# PCA9685_sheet.net
KiCad netlist of a schematic drawn in Altium Designer
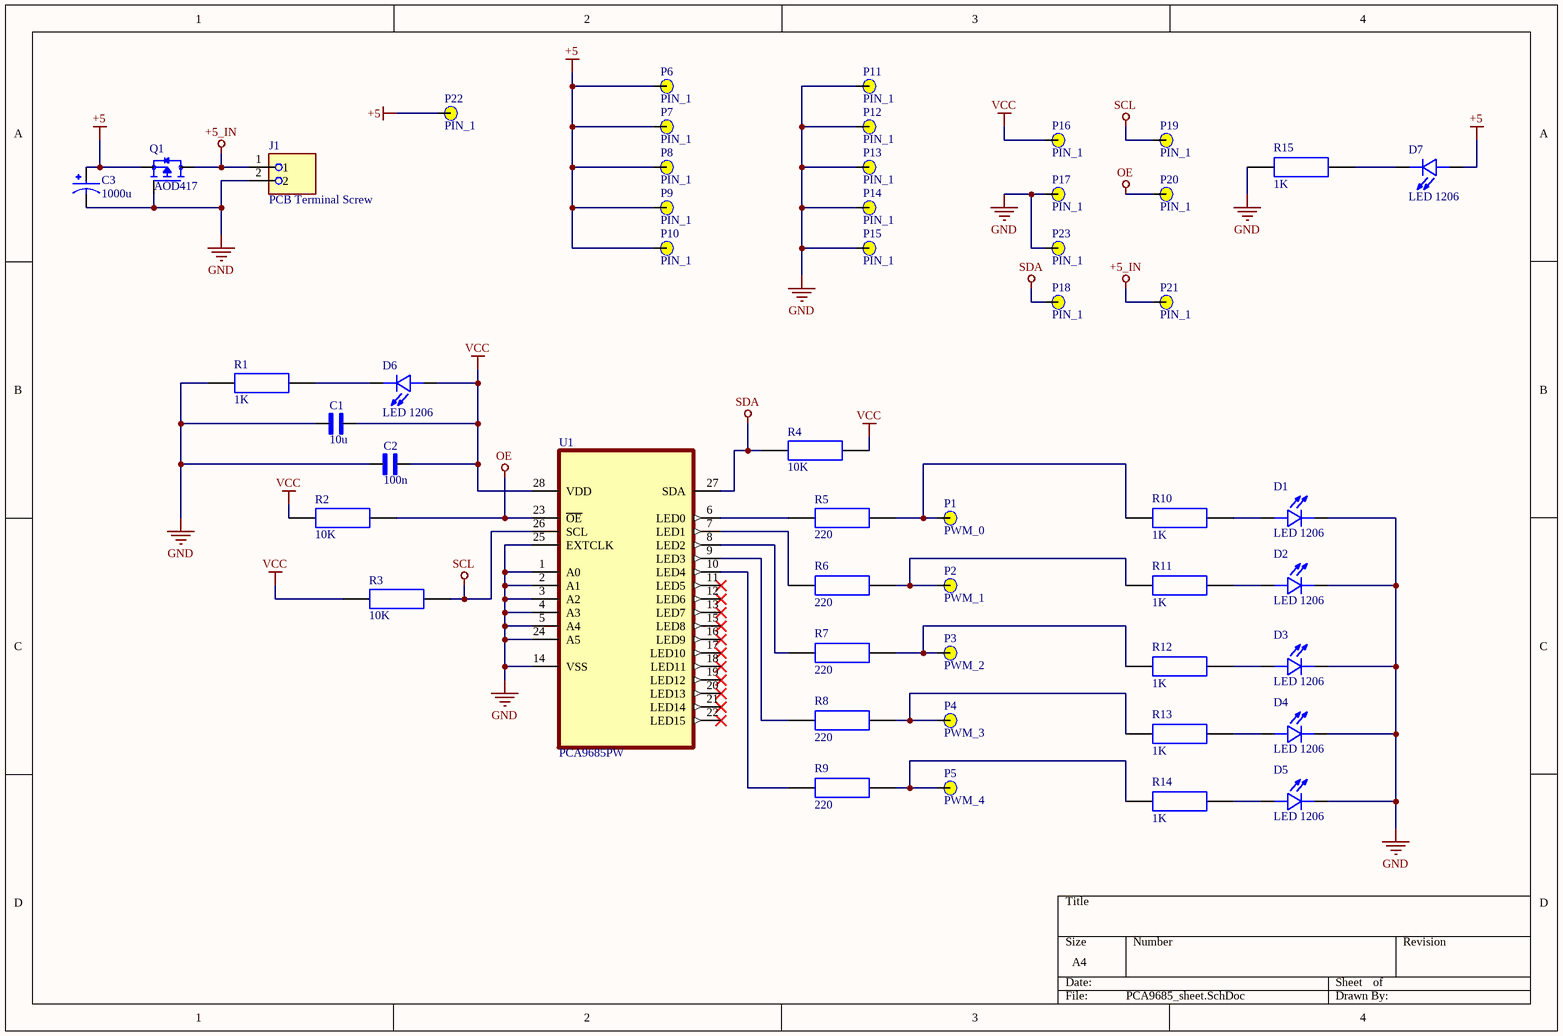
[diagram p0: PCA9685_sheet.SchDoc]

(export (version "E")
  (design (tool "Eeschema 10.0.6"))
  (components
    (comp (ref "C1")
      (value "10u")
      (footprint "Capacitor 1206")
      (fields (field (name "MF") "AVX") (field (name "MP") "12061C225K4T2A"))
      (libsource (lib "PCA_9685_lib") (part "Capacitor 1206"))
    )
    (comp (ref "C2")
      (value "100n")
      (footprint "Capacitor 1206")
      (fields (field (name "MF") "AVX") (field (name "MP") "12061C225K4T2A"))
      (libsource (lib "PCA_9685_lib") (part "Capacitor 1206"))
    )
    (comp (ref "C3")
      (value "1000u")
      (footprint "Electrolytic capacitor")
      (fields (field (name "MP") "EEUFR1A102LB") (field (name "MF") "Panasonic"))
      (libsource (lib "PCA_9685_lib") (part "Electrolytic capacitor"))
    )
    (comp (ref "D1")
      (value "LED 1206")
      (footprint "LED 1206")
      (fields (field (name "MF") "Lite-On Inc.") (field (name "MP") "LTST-C230KGKT"))
      (libsource (lib "PCA_9685_lib") (part "LED 1206"))
    )
    (comp (ref "D2")
      (value "LED 1206")
      (footprint "LED 1206")
      (fields (field (name "MF") "Lite-On Inc.") (field (name "MP") "LTST-C230KGKT"))
      (libsource (lib "PCA_9685_lib") (part "LED 1206"))
    )
    (comp (ref "D3")
      (value "LED 1206")
      (footprint "LED 1206")
      (fields (field (name "MF") "Lite-On Inc.") (field (name "MP") "LTST-C230KGKT"))
      (libsource (lib "PCA_9685_lib") (part "LED 1206"))
    )
    (comp (ref "D4")
      (value "LED 1206")
      (footprint "LED 1206")
      (fields (field (name "MF") "Lite-On Inc.") (field (name "MP") "LTST-C230KGKT"))
      (libsource (lib "PCA_9685_lib") (part "LED 1206"))
    )
    (comp (ref "D5")
      (value "LED 1206")
      (footprint "LED 1206")
      (fields (field (name "MF") "Lite-On Inc.") (field (name "MP") "LTST-C230KGKT"))
      (libsource (lib "PCA_9685_lib") (part "LED 1206"))
    )
    (comp (ref "D6")
      (value "LED 1206")
      (footprint "LED 1206")
      (fields (field (name "MF") "Lite-On Inc.") (field (name "MP") "LTST-C230KGKT"))
      (libsource (lib "") (part "LED 1206_1"))
    )
    (comp (ref "D7")
      (value "LED 1206")
      (footprint "LED 1206")
      (fields (field (name "MF") "Lite-On Inc.") (field (name "MP") "LTST-C230KGKT"))
      (libsource (lib "") (part "LED 1206_1"))
    )
    (comp (ref "J1")
      (value "PCB Terminal Screw")
      (footprint "PCB Terminal Screw")
      (fields (field (name "MF") "Phoenix Contact") (field (name "MP") "1729128"))
      (libsource (lib "PCA_9685_lib") (part "PCB Terminal Screw"))
    )
    (comp (ref "P1") (value "PWM_0") (footprint "PCB_Pin_1") (libsource (lib "PCA_9685_lib") (part "PIN_1")))
    (comp (ref "P2") (value "PWM_1") (footprint "PCB_Pin_1") (libsource (lib "PCA_9685_lib") (part "PIN_1")))
    (comp (ref "P3") (value "PWM_2") (footprint "PCB_Pin_1") (libsource (lib "PCA_9685_lib") (part "PIN_1")))
    (comp (ref "P4") (value "PWM_3") (footprint "PCB_Pin_1") (libsource (lib "PCA_9685_lib") (part "PIN_1")))
    (comp (ref "P5") (value "PWM_4") (footprint "PCB_Pin_1") (libsource (lib "PCA_9685_lib") (part "PIN_1")))
    (comp (ref "P6") (value "PIN_1") (footprint "PCB_Pin_1") (libsource (lib "PCA_9685_lib") (part "PIN_1")))
    (comp (ref "P7") (value "PIN_1") (footprint "PCB_Pin_1") (libsource (lib "PCA_9685_lib") (part "PIN_1")))
    (comp (ref "P8") (value "PIN_1") (footprint "PCB_Pin_1") (libsource (lib "PCA_9685_lib") (part "PIN_1")))
    (comp (ref "P9") (value "PIN_1") (footprint "PCB_Pin_1") (libsource (lib "PCA_9685_lib") (part "PIN_1")))
    (comp (ref "P10") (value "PIN_1") (footprint "PCB_Pin_1") (libsource (lib "PCA_9685_lib") (part "PIN_1")))
    (comp (ref "P11") (value "PIN_1") (footprint "PCB_Pin_1") (libsource (lib "PCA_9685_lib") (part "PIN_1")))
    (comp (ref "P12") (value "PIN_1") (footprint "PCB_Pin_1") (libsource (lib "PCA_9685_lib") (part "PIN_1")))
    (comp (ref "P13") (value "PIN_1") (footprint "PCB_Pin_1") (libsource (lib "PCA_9685_lib") (part "PIN_1")))
    (comp (ref "P14") (value "PIN_1") (footprint "PCB_Pin_1") (libsource (lib "PCA_9685_lib") (part "PIN_1")))
    (comp (ref "P15") (value "PIN_1") (footprint "PCB_Pin_1") (libsource (lib "PCA_9685_lib") (part "PIN_1")))
    (comp (ref "P16") (value "PIN_1") (footprint "PCB_Pin_1") (libsource (lib "PCA_9685_lib") (part "PIN_1")))
    (comp (ref "P17") (value "PIN_1") (footprint "PCB_Pin_1") (libsource (lib "PCA_9685_lib") (part "PIN_1")))
    (comp (ref "P18") (value "PIN_1") (footprint "PCB_Pin_1") (libsource (lib "PCA_9685_lib") (part "PIN_1")))
    (comp (ref "P19") (value "PIN_1") (footprint "PCB_Pin_1") (libsource (lib "PCA_9685_lib") (part "PIN_1")))
    (comp (ref "P20") (value "PIN_1") (footprint "PCB_Pin_1") (libsource (lib "PCA_9685_lib") (part "PIN_1")))
    (comp (ref "P21") (value "PIN_1") (footprint "PCB_Pin_1") (libsource (lib "PCA_9685_lib") (part "PIN_1")))
    (comp (ref "P22") (value "PIN_1") (footprint "PCB_Pin_1") (libsource (lib "PCA_9685_lib") (part "PIN_1")))
    (comp (ref "P23") (value "PIN_1") (footprint "PCB_Pin_1") (libsource (lib "PCA_9685_lib") (part "PIN_1")))
    (comp (ref "Q1")
      (value "AOD417")
      (footprint "PCA_9685_lib:Transistor AOD417")
      (fields (field (name "MF") "Alpha &"))
      (libsource (lib "PCA_9685_lib") (part "Transistor AOD417"))
    )
    (comp (ref "R1")
      (value "1K")
      (footprint "PCA_9685_lib:Resistor 1206")
      (fields (field (name "MP") "ERJU08F4703V"))
      (libsource (lib "PCA_9685_lib") (part "Resistor 1206"))
    )
    (comp (ref "R2")
      (value "10K")
      (footprint "PCA_9685_lib:Resistor 1206")
      (fields (field (name "MP") "ERJU08F4703V"))
      (libsource (lib "PCA_9685_lib") (part "Resistor 1206"))
    )
    (comp (ref "R3")
      (value "10K")
      (footprint "PCA_9685_lib:Resistor 1206")
      (fields (field (name "MP") "ERJU08F4703V"))
      (libsource (lib "PCA_9685_lib") (part "Resistor 1206"))
    )
    (comp (ref "R4")
      (value "10K")
      (footprint "PCA_9685_lib:Resistor 1206")
      (fields (field (name "MP") "ERJU08F4703V"))
      (libsource (lib "PCA_9685_lib") (part "Resistor 1206"))
    )
    (comp (ref "R5")
      (value "220")
      (footprint "PCA_9685_lib:Resistor 1206")
      (fields (field (name "MP") "ERJU08F4703V"))
      (libsource (lib "PCA_9685_lib") (part "Resistor 1206"))
    )
    (comp (ref "R6")
      (value "220")
      (footprint "PCA_9685_lib:Resistor 1206")
      (fields (field (name "MP") "ERJU08F4703V"))
      (libsource (lib "PCA_9685_lib") (part "Resistor 1206"))
    )
    (comp (ref "R7")
      (value "220")
      (footprint "PCA_9685_lib:Resistor 1206")
      (fields (field (name "MP") "ERJU08F4703V"))
      (libsource (lib "PCA_9685_lib") (part "Resistor 1206"))
    )
    (comp (ref "R8")
      (value "220")
      (footprint "PCA_9685_lib:Resistor 1206")
      (fields (field (name "MP") "ERJU08F4703V"))
      (libsource (lib "PCA_9685_lib") (part "Resistor 1206"))
    )
    (comp (ref "R9")
      (value "220")
      (footprint "PCA_9685_lib:Resistor 1206")
      (fields (field (name "MP") "ERJU08F4703V"))
      (libsource (lib "PCA_9685_lib") (part "Resistor 1206"))
    )
    (comp (ref "R10")
      (value "1K")
      (footprint "PCA_9685_lib:Resistor 1206")
      (fields (field (name "MP") "ERJU08F4703V"))
      (libsource (lib "PCA_9685_lib") (part "Resistor 1206"))
    )
    (comp (ref "R11")
      (value "1K")
      (footprint "PCA_9685_lib:Resistor 1206")
      (fields (field (name "MP") "ERJU08F4703V"))
      (libsource (lib "PCA_9685_lib") (part "Resistor 1206"))
    )
    (comp (ref "R12")
      (value "1K")
      (footprint "PCA_9685_lib:Resistor 1206")
      (fields (field (name "MP") "ERJU08F4703V"))
      (libsource (lib "PCA_9685_lib") (part "Resistor 1206"))
    )
    (comp (ref "R13")
      (value "1K")
      (footprint "PCA_9685_lib:Resistor 1206")
      (fields (field (name "MP") "ERJU08F4703V"))
      (libsource (lib "PCA_9685_lib") (part "Resistor 1206"))
    )
    (comp (ref "R14")
      (value "1K")
      (footprint "PCA_9685_lib:Resistor 1206")
      (fields (field (name "MP") "ERJU08F4703V"))
      (libsource (lib "PCA_9685_lib") (part "Resistor 1206"))
    )
    (comp (ref "R15")
      (value "1K")
      (footprint "PCA_9685_lib:Resistor 1206")
      (fields (field (name "MP") "ERJU08F4703V"))
      (libsource (lib "PCA_9685_lib") (part "Resistor 1206"))
    )
    (comp (ref "U1")
      (value "PCA9685PW")
      (footprint "PCA9685PW")
      (fields (field (name "MF") "NXP USA") (field (name "MP") "PCA9685PW,118"))
      (libsource (lib "PCA_9685_lib") (part "PCA9685PW"))
    )
  )
  (nets
    (net (code "1") (name "+5") (class "Default")
      (node (ref "C3") (pin "P") (pinfunction "P_P") (pintype "passive"))
      (node (ref "D7") (pin "A") (pinfunction "A_A") (pintype "passive"))
      (node (ref "P10") (pin "0") (pinfunction "Pin_0") (pintype "passive"))
      (node (ref "P22") (pin "0") (pinfunction "Pin_0") (pintype "passive"))
      (node (ref "P6") (pin "0") (pinfunction "Pin_0") (pintype "passive"))
      (node (ref "P7") (pin "0") (pinfunction "Pin_0") (pintype "passive"))
      (node (ref "P8") (pin "0") (pinfunction "Pin_0") (pintype "passive"))
      (node (ref "P9") (pin "0") (pinfunction "Pin_0") (pintype "passive"))
      (node (ref "Q1") (pin "3") (pinfunction "S_3") (pintype "passive"))
    )
    (net (code "2") (name "+5_IN") (class "Default")
      (node (ref "J1") (pin "1") (pinfunction "1_1") (pintype "passive"))
      (node (ref "P21") (pin "0") (pinfunction "Pin_0") (pintype "passive"))
      (node (ref "Q1") (pin "4") (pinfunction "D_4") (pintype "passive"))
    )
    (net (code "3") (name "GND") (class "Default")
      (node (ref "C1") (pin "1") (pinfunction "1_1") (pintype "passive"))
      (node (ref "C2") (pin "1") (pinfunction "1_1") (pintype "passive"))
      (node (ref "C3") (pin "N") (pinfunction "N_N") (pintype "passive"))
      (node (ref "D1") (pin "C") (pinfunction "C_C") (pintype "passive"))
      (node (ref "D2") (pin "C") (pinfunction "C_C") (pintype "passive"))
      (node (ref "D3") (pin "C") (pinfunction "C_C") (pintype "passive"))
      (node (ref "D4") (pin "C") (pinfunction "C_C") (pintype "passive"))
      (node (ref "D5") (pin "C") (pinfunction "C_C") (pintype "passive"))
      (node (ref "J1") (pin "2") (pinfunction "2_2") (pintype "passive"))
      (node (ref "P11") (pin "0") (pinfunction "Pin_0") (pintype "passive"))
      (node (ref "P12") (pin "0") (pinfunction "Pin_0") (pintype "passive"))
      (node (ref "P13") (pin "0") (pinfunction "Pin_0") (pintype "passive"))
      (node (ref "P14") (pin "0") (pinfunction "Pin_0") (pintype "passive"))
      (node (ref "P15") (pin "0") (pinfunction "Pin_0") (pintype "passive"))
      (node (ref "P17") (pin "0") (pinfunction "Pin_0") (pintype "passive"))
      (node (ref "P23") (pin "0") (pinfunction "Pin_0") (pintype "passive"))
      (node (ref "Q1") (pin "1") (pinfunction "G_1") (pintype "passive"))
      (node (ref "R1") (pin "1") (pinfunction "1_1") (pintype "passive"))
      (node (ref "R15") (pin "1") (pinfunction "1_1") (pintype "passive"))
      (node (ref "U1") (pin "1") (pinfunction "A0_1") (pintype "passive"))
      (node (ref "U1") (pin "14") (pinfunction "VSS_14") (pintype "passive"))
      (node (ref "U1") (pin "2") (pinfunction "A1_2") (pintype "passive"))
      (node (ref "U1") (pin "24") (pinfunction "A5_24") (pintype "passive"))
      (node (ref "U1") (pin "25") (pinfunction "EXTCLK_25") (pintype "passive"))
      (node (ref "U1") (pin "3") (pinfunction "A2_3") (pintype "passive"))
      (node (ref "U1") (pin "4") (pinfunction "A3_4") (pintype "passive"))
      (node (ref "U1") (pin "5") (pinfunction "A4_5") (pintype "passive"))
    )
    (net (code "4") (name "Net-(D1-PadA)") (class "Default")
      (node (ref "D1") (pin "A") (pinfunction "A_A") (pintype "passive"))
      (node (ref "R10") (pin "2") (pinfunction "2_2") (pintype "passive"))
    )
    (net (code "5") (name "Net-(D2-PadA)") (class "Default")
      (node (ref "D2") (pin "A") (pinfunction "A_A") (pintype "passive"))
      (node (ref "R11") (pin "2") (pinfunction "2_2") (pintype "passive"))
    )
    (net (code "6") (name "Net-(D3-PadA)") (class "Default")
      (node (ref "D3") (pin "A") (pinfunction "A_A") (pintype "passive"))
      (node (ref "R12") (pin "2") (pinfunction "2_2") (pintype "passive"))
    )
    (net (code "7") (name "Net-(D4-PadA)") (class "Default")
      (node (ref "D4") (pin "A") (pinfunction "A_A") (pintype "passive"))
      (node (ref "R13") (pin "2") (pinfunction "2_2") (pintype "passive"))
    )
    (net (code "8") (name "Net-(D5-PadA)") (class "Default")
      (node (ref "D5") (pin "A") (pinfunction "A_A") (pintype "passive"))
      (node (ref "R14") (pin "2") (pinfunction "2_2") (pintype "passive"))
    )
    (net (code "9") (name "Net-(D6-PadC)") (class "Default")
      (node (ref "D6") (pin "C") (pinfunction "C_C") (pintype "passive"))
      (node (ref "R1") (pin "2") (pinfunction "2_2") (pintype "passive"))
    )
    (net (code "10") (name "Net-(D7-PadC)") (class "Default")
      (node (ref "D7") (pin "C") (pinfunction "C_C") (pintype "passive"))
      (node (ref "R15") (pin "2") (pinfunction "2_2") (pintype "passive"))
    )
    (net (code "11") (name "Net-(P1-Pin)") (class "Default")
      (node (ref "P1") (pin "0") (pinfunction "Pin_0") (pintype "passive"))
      (node (ref "R10") (pin "1") (pinfunction "1_1") (pintype "passive"))
      (node (ref "R5") (pin "2") (pinfunction "2_2") (pintype "passive"))
    )
    (net (code "12") (name "Net-(P2-Pin)") (class "Default")
      (node (ref "P2") (pin "0") (pinfunction "Pin_0") (pintype "passive"))
      (node (ref "R11") (pin "1") (pinfunction "1_1") (pintype "passive"))
      (node (ref "R6") (pin "2") (pinfunction "2_2") (pintype "passive"))
    )
    (net (code "13") (name "Net-(P3-Pin)") (class "Default")
      (node (ref "P3") (pin "0") (pinfunction "Pin_0") (pintype "passive"))
      (node (ref "R12") (pin "1") (pinfunction "1_1") (pintype "passive"))
      (node (ref "R7") (pin "2") (pinfunction "2_2") (pintype "passive"))
    )
    (net (code "14") (name "Net-(P4-Pin)") (class "Default")
      (node (ref "P4") (pin "0") (pinfunction "Pin_0") (pintype "passive"))
      (node (ref "R13") (pin "1") (pinfunction "1_1") (pintype "passive"))
      (node (ref "R8") (pin "2") (pinfunction "2_2") (pintype "passive"))
    )
    (net (code "15") (name "Net-(P5-Pin)") (class "Default")
      (node (ref "P5") (pin "0") (pinfunction "Pin_0") (pintype "passive"))
      (node (ref "R14") (pin "1") (pinfunction "1_1") (pintype "passive"))
      (node (ref "R9") (pin "2") (pinfunction "2_2") (pintype "passive"))
    )
    (net (code "16") (name "Net-(U1-LED0)") (class "Default")
      (node (ref "R5") (pin "1") (pinfunction "1_1") (pintype "passive"))
      (node (ref "U1") (pin "6") (pinfunction "LED0_6") (pintype "output"))
    )
    (net (code "17") (name "Net-(U1-LED1)") (class "Default")
      (node (ref "R6") (pin "1") (pinfunction "1_1") (pintype "passive"))
      (node (ref "U1") (pin "7") (pinfunction "LED1_7") (pintype "output"))
    )
    (net (code "18") (name "Net-(U1-LED2)") (class "Default")
      (node (ref "R7") (pin "1") (pinfunction "1_1") (pintype "passive"))
      (node (ref "U1") (pin "8") (pinfunction "LED2_8") (pintype "output"))
    )
    (net (code "19") (name "Net-(U1-LED3)") (class "Default")
      (node (ref "R8") (pin "1") (pinfunction "1_1") (pintype "passive"))
      (node (ref "U1") (pin "9") (pinfunction "LED3_9") (pintype "output"))
    )
    (net (code "20") (name "Net-(U1-LED4)") (class "Default")
      (node (ref "R9") (pin "1") (pinfunction "1_1") (pintype "passive"))
      (node (ref "U1") (pin "10") (pinfunction "LED4_10") (pintype "output"))
    )
    (net (code "21") (name "OE") (class "Default")
      (node (ref "P20") (pin "0") (pinfunction "Pin_0") (pintype "passive"))
      (node (ref "R2") (pin "2") (pinfunction "2_2") (pintype "passive"))
      (node (ref "U1") (pin "23") (pinfunction "~{OE}_23") (pintype "passive"))
    )
    (net (code "22") (name "SCL") (class "Default")
      (node (ref "P19") (pin "0") (pinfunction "Pin_0") (pintype "passive"))
      (node (ref "R3") (pin "2") (pinfunction "2_2") (pintype "passive"))
      (node (ref "U1") (pin "26") (pinfunction "SCL_26") (pintype "passive"))
    )
    (net (code "23") (name "SDA") (class "Default")
      (node (ref "P18") (pin "0") (pinfunction "Pin_0") (pintype "passive"))
      (node (ref "R4") (pin "1") (pinfunction "1_1") (pintype "passive"))
      (node (ref "U1") (pin "27") (pinfunction "SDA_27") (pintype "passive"))
    )
    (net (code "24") (name "VCC") (class "Default")
      (node (ref "C1") (pin "2") (pinfunction "2_2") (pintype "passive"))
      (node (ref "C2") (pin "2") (pinfunction "2_2") (pintype "passive"))
      (node (ref "D6") (pin "A") (pinfunction "A_A") (pintype "passive"))
      (node (ref "P16") (pin "0") (pinfunction "Pin_0") (pintype "passive"))
      (node (ref "R2") (pin "1") (pinfunction "1_1") (pintype "passive"))
      (node (ref "R3") (pin "1") (pinfunction "1_1") (pintype "passive"))
      (node (ref "R4") (pin "2") (pinfunction "2_2") (pintype "passive"))
      (node (ref "U1") (pin "28") (pinfunction "VDD_28") (pintype "power_in"))
    )
    (net (code "25") (name "unconnected-(U1-LED5-Pad11)") (class "Default")
      (node (ref "U1") (pin "11") (pinfunction "LED5_11") (pintype "output+no_connect"))
    )
    (net (code "26") (name "unconnected-(U1-LED6-Pad12)") (class "Default")
      (node (ref "U1") (pin "12") (pinfunction "LED6_12") (pintype "output+no_connect"))
    )
    (net (code "27") (name "unconnected-(U1-LED7-Pad13)") (class "Default")
      (node (ref "U1") (pin "13") (pinfunction "LED7_13") (pintype "output+no_connect"))
    )
    (net (code "28") (name "unconnected-(U1-LED8-Pad15)") (class "Default")
      (node (ref "U1") (pin "15") (pinfunction "LED8_15") (pintype "output+no_connect"))
    )
    (net (code "29") (name "unconnected-(U1-LED9-Pad16)") (class "Default")
      (node (ref "U1") (pin "16") (pinfunction "LED9_16") (pintype "output+no_connect"))
    )
    (net (code "30") (name "unconnected-(U1-LED10-Pad17)") (class "Default")
      (node (ref "U1") (pin "17") (pinfunction "LED10_17") (pintype "output+no_connect"))
    )
    (net (code "31") (name "unconnected-(U1-LED11-Pad18)") (class "Default")
      (node (ref "U1") (pin "18") (pinfunction "LED11_18") (pintype "output+no_connect"))
    )
    (net (code "32") (name "unconnected-(U1-LED12-Pad19)") (class "Default")
      (node (ref "U1") (pin "19") (pinfunction "LED12_19") (pintype "output+no_connect"))
    )
    (net (code "33") (name "unconnected-(U1-LED13-Pad20)") (class "Default")
      (node (ref "U1") (pin "20") (pinfunction "LED13_20") (pintype "output+no_connect"))
    )
    (net (code "34") (name "unconnected-(U1-LED14-Pad21)") (class "Default")
      (node (ref "U1") (pin "21") (pinfunction "LED14_21") (pintype "output+no_connect"))
    )
    (net (code "35") (name "unconnected-(U1-LED15-Pad22)") (class "Default")
      (node (ref "U1") (pin "22") (pinfunction "LED15_22") (pintype "output+no_connect"))
    )
  )
)
